# Odbiornik_1.net
KiCad netlist of a schematic drawn in EAGLE
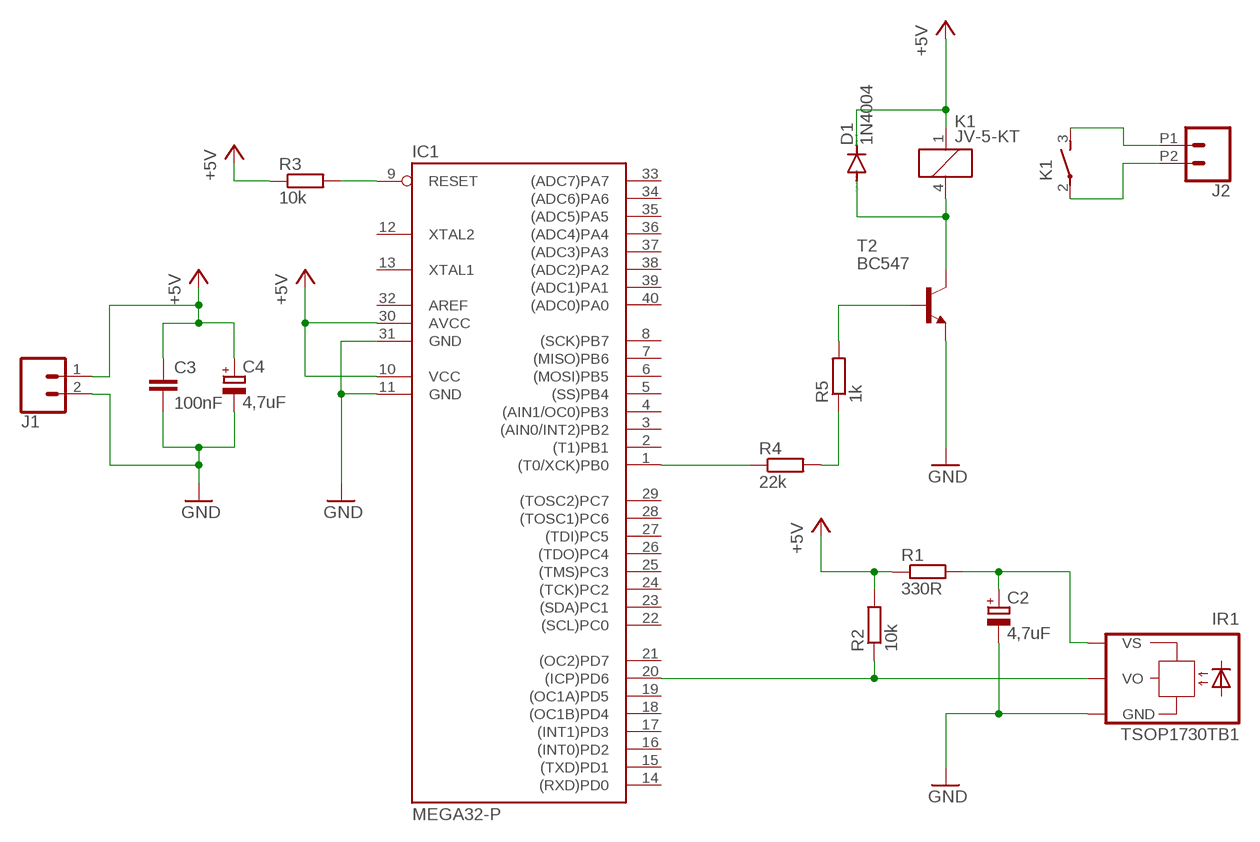
[diagram p0: schematic, sheet 1]

(export (version "E")
  (design (tool "Eeschema 10.0.6"))
  (components
    (comp (ref "C2")
      (value "4,7uF")
      (footprint "eagle-import:E2-4")
      (libsource (lib "eagle-import") (part "CPOL-EUE2-4"))
    )
    (comp (ref "C3")
      (value "100nF")
      (footprint "eagle-import:C025-024X044")
      (libsource (lib "eagle-import") (part "C-EU025-024X044"))
    )
    (comp (ref "C4")
      (value "4,7uF")
      (footprint "eagle-import:E2-4")
      (libsource (lib "eagle-import") (part "CPOL-EUE2-4"))
    )
    (comp (ref "D1")
      (value "1N4004")
      (footprint "eagle-import:DO41-10")
      (libsource (lib "eagle-import") (part "1N4004"))
    )
    (comp (ref "IC1")
      (value "MEGA32-P")
      (footprint "eagle-import:DIL40")
      (fields (field (name "MPN") "ATMEGA32-16PU"))
      (libsource (lib "eagle-import") (part "MEGA32-P"))
    )
    (comp (ref "IR1")
      (value "TSOP1730TB1")
      (footprint "eagle-import:TSOP17_TB1")
      (libsource (lib "eagle-import") (part "TSOP17TB130"))
    )
    (comp (ref "J1")
      (value "CONN_02")
      (footprint "eagle-import:1X02")
      (libsource (lib "eagle-import") (part "CONN_02"))
    )
    (comp (ref "J2")
      (value "CONN_022.54MM_SCREWTERM")
      (footprint "eagle-import:1X02_2.54_SCREWTERM")
      (libsource (lib "eagle-import") (part "CONN_022.54MM_SCREWTERM"))
    )
    (comp (ref "K1")
      (value "JV-5-KT")
      (footprint "eagle-import:JV-KT")
      (libsource (lib "eagle-import") (part "JV-KT-5"))
    )
    (comp (ref "R1")
      (value "330R")
      (footprint "eagle-import:0204_5")
      (libsource (lib "eagle-import") (part "R-EU_0204/5"))
    )
    (comp (ref "R2")
      (value "10k")
      (footprint "eagle-import:0204_5")
      (libsource (lib "eagle-import") (part "R-EU_0204/5"))
    )
    (comp (ref "R3")
      (value "10k")
      (footprint "eagle-import:0204_5")
      (libsource (lib "eagle-import") (part "R-EU_0204/5"))
    )
    (comp (ref "R4")
      (value "22k")
      (footprint "eagle-import:0204_5")
      (libsource (lib "eagle-import") (part "R-EU_0204/5"))
    )
    (comp (ref "R5")
      (value "1k")
      (footprint "eagle-import:0204_5")
      (libsource (lib "eagle-import") (part "R-EU_0204/5"))
    )
    (comp (ref "T2")
      (value "BC547")
      (footprint "eagle-import:TO92")
      (libsource (lib "eagle-import") (part "BC547"))
    )
  )
  (nets
    (net (code "1") (name "+5V") (class "Default")
      (node (ref "C3") (pin "1") (pinfunction "1_1") (pintype "passive"))
      (node (ref "C4") (pin "+") (pinfunction "+_+") (pintype "passive"))
      (node (ref "D1") (pin "C") (pinfunction "C_C") (pintype "passive"))
      (node (ref "IC1") (pin "10") (pinfunction "VCC_10") (pintype "power_in"))
      (node (ref "IC1") (pin "30") (pinfunction "AVCC_30") (pintype "power_in"))
      (node (ref "J1") (pin "1") (pinfunction "1_1") (pintype "passive"))
      (node (ref "K1") (pin "1") (pinfunction "1_1") (pintype "passive"))
      (node (ref "R1") (pin "1") (pinfunction "1_1") (pintype "passive"))
      (node (ref "R2") (pin "2") (pinfunction "2_2") (pintype "passive"))
      (node (ref "R3") (pin "1") (pinfunction "1_1") (pintype "passive"))
    )
    (net (code "2") (name "GND") (class "Default")
      (node (ref "C2") (pin "-") (pinfunction "-_-") (pintype "passive"))
      (node (ref "C3") (pin "2") (pinfunction "2_2") (pintype "passive"))
      (node (ref "C4") (pin "-") (pinfunction "-_-") (pintype "passive"))
      (node (ref "IC1") (pin "11") (pinfunction "GND_11") (pintype "power_in"))
      (node (ref "IC1") (pin "31") (pinfunction "GND_31") (pintype "power_in"))
      (node (ref "IR1") (pin "GND") (pinfunction "GND_GND") (pintype "power_in"))
      (node (ref "J1") (pin "2") (pinfunction "2_2") (pintype "passive"))
      (node (ref "T2") (pin "1") (pinfunction "E_1") (pintype "passive"))
    )
    (net (code "3") (name "Net-(C2-Pad+)") (class "Default")
      (node (ref "C2") (pin "+") (pinfunction "+_+") (pintype "passive"))
      (node (ref "IR1") (pin "VS") (pinfunction "VS_VS") (pintype "power_in"))
      (node (ref "R1") (pin "2") (pinfunction "2_2") (pintype "passive"))
    )
    (net (code "4") (name "Net-(IC1-(ICP)PD6)") (class "Default")
      (node (ref "IC1") (pin "20") (pinfunction "(ICP)PD6_20") (pintype "bidirectional"))
      (node (ref "IR1") (pin "VO") (pinfunction "VO_VO") (pintype "open_collector"))
      (node (ref "R2") (pin "1") (pinfunction "1_1") (pintype "passive"))
    )
    (net (code "5") (name "Net-(IC1-(T0{slash}XCK)PB0)") (class "Default")
      (node (ref "IC1") (pin "1") (pinfunction "(T0/XCK)PB0_1") (pintype "bidirectional"))
      (node (ref "R4") (pin "1") (pinfunction "1_1") (pintype "passive"))
    )
    (net (code "6") (name "Net-(IC1-RESET)") (class "Default")
      (node (ref "IC1") (pin "9") (pinfunction "RESET_9") (pintype "input"))
      (node (ref "R3") (pin "2") (pinfunction "2_2") (pintype "passive"))
    )
    (net (code "7") (name "Net-(J2-1)") (class "Default")
      (node (ref "J2") (pin "P1") (pinfunction "1_P1") (pintype "passive"))
      (node (ref "K1") (pin "3") (pinfunction "S_3") (pintype "passive"))
    )
    (net (code "8") (name "Net-(J2-2)") (class "Default")
      (node (ref "J2") (pin "P2") (pinfunction "2_P2") (pintype "passive"))
      (node (ref "K1") (pin "2") (pinfunction "P_2") (pintype "passive"))
    )
    (net (code "9") (name "Net-(K1A-2)") (class "Default")
      (node (ref "D1") (pin "A") (pinfunction "A_A") (pintype "passive"))
      (node (ref "K1") (pin "4") (pinfunction "2_4") (pintype "passive"))
      (node (ref "T2") (pin "3") (pinfunction "C_3") (pintype "passive"))
    )
    (net (code "10") (name "Net-(R4-Pad2)") (class "Default")
      (node (ref "R4") (pin "2") (pinfunction "2_2") (pintype "passive"))
      (node (ref "R5") (pin "1") (pinfunction "1_1") (pintype "passive"))
    )
    (net (code "11") (name "Net-(T2-B)") (class "Default")
      (node (ref "R5") (pin "2") (pinfunction "2_2") (pintype "passive"))
      (node (ref "T2") (pin "2") (pinfunction "B_2") (pintype "passive"))
    )
    (net (code "12") (name "unconnected-(IC1-(ADC0)PA0-Pad40)") (class "Default")
      (node (ref "IC1") (pin "40") (pinfunction "(ADC0)PA0_40") (pintype "bidirectional"))
    )
    (net (code "13") (name "unconnected-(IC1-(ADC1)PA1-Pad39)") (class "Default")
      (node (ref "IC1") (pin "39") (pinfunction "(ADC1)PA1_39") (pintype "bidirectional"))
    )
    (net (code "14") (name "unconnected-(IC1-(ADC2)PA2-Pad38)") (class "Default")
      (node (ref "IC1") (pin "38") (pinfunction "(ADC2)PA2_38") (pintype "bidirectional"))
    )
    (net (code "15") (name "unconnected-(IC1-(ADC3)PA3-Pad37)") (class "Default")
      (node (ref "IC1") (pin "37") (pinfunction "(ADC3)PA3_37") (pintype "bidirectional"))
    )
    (net (code "16") (name "unconnected-(IC1-(ADC4)PA4-Pad36)") (class "Default")
      (node (ref "IC1") (pin "36") (pinfunction "(ADC4)PA4_36") (pintype "bidirectional"))
    )
    (net (code "17") (name "unconnected-(IC1-(ADC5)PA5-Pad35)") (class "Default")
      (node (ref "IC1") (pin "35") (pinfunction "(ADC5)PA5_35") (pintype "bidirectional"))
    )
    (net (code "18") (name "unconnected-(IC1-(ADC6)PA6-Pad34)") (class "Default")
      (node (ref "IC1") (pin "34") (pinfunction "(ADC6)PA6_34") (pintype "bidirectional"))
    )
    (net (code "19") (name "unconnected-(IC1-(ADC7)PA7-Pad33)") (class "Default")
      (node (ref "IC1") (pin "33") (pinfunction "(ADC7)PA7_33") (pintype "bidirectional"))
    )
    (net (code "20") (name "unconnected-(IC1-(AIN0{slash}INT2)PB2-Pad3)") (class "Default")
      (node (ref "IC1") (pin "3") (pinfunction "(AIN0/INT2)PB2_3") (pintype "bidirectional"))
    )
    (net (code "21") (name "unconnected-(IC1-(AIN1{slash}OC0)PB3-Pad4)") (class "Default")
      (node (ref "IC1") (pin "4") (pinfunction "(AIN1/OC0)PB3_4") (pintype "bidirectional"))
    )
    (net (code "22") (name "unconnected-(IC1-(INT0)PD2-Pad16)") (class "Default")
      (node (ref "IC1") (pin "16") (pinfunction "(INT0)PD2_16") (pintype "bidirectional"))
    )
    (net (code "23") (name "unconnected-(IC1-(INT1)PD3-Pad17)") (class "Default")
      (node (ref "IC1") (pin "17") (pinfunction "(INT1)PD3_17") (pintype "bidirectional"))
    )
    (net (code "24") (name "unconnected-(IC1-(MISO)PB6-Pad7)") (class "Default")
      (node (ref "IC1") (pin "7") (pinfunction "(MISO)PB6_7") (pintype "bidirectional"))
    )
    (net (code "25") (name "unconnected-(IC1-(MOSI)PB5-Pad6)") (class "Default")
      (node (ref "IC1") (pin "6") (pinfunction "(MOSI)PB5_6") (pintype "bidirectional"))
    )
    (net (code "26") (name "unconnected-(IC1-(OC1A)PD5-Pad19)") (class "Default")
      (node (ref "IC1") (pin "19") (pinfunction "(OC1A)PD5_19") (pintype "bidirectional"))
    )
    (net (code "27") (name "unconnected-(IC1-(OC1B)PD4-Pad18)") (class "Default")
      (node (ref "IC1") (pin "18") (pinfunction "(OC1B)PD4_18") (pintype "bidirectional"))
    )
    (net (code "28") (name "unconnected-(IC1-(OC2)PD7-Pad21)") (class "Default")
      (node (ref "IC1") (pin "21") (pinfunction "(OC2)PD7_21") (pintype "bidirectional"))
    )
    (net (code "29") (name "unconnected-(IC1-(RXD)PD0-Pad14)") (class "Default")
      (node (ref "IC1") (pin "14") (pinfunction "(RXD)PD0_14") (pintype "bidirectional"))
    )
    (net (code "30") (name "unconnected-(IC1-(SCK)PB7-Pad8)") (class "Default")
      (node (ref "IC1") (pin "8") (pinfunction "(SCK)PB7_8") (pintype "bidirectional"))
    )
    (net (code "31") (name "unconnected-(IC1-(SCL)PC0-Pad22)") (class "Default")
      (node (ref "IC1") (pin "22") (pinfunction "(SCL)PC0_22") (pintype "bidirectional"))
    )
    (net (code "32") (name "unconnected-(IC1-(SDA)PC1-Pad23)") (class "Default")
      (node (ref "IC1") (pin "23") (pinfunction "(SDA)PC1_23") (pintype "bidirectional"))
    )
    (net (code "33") (name "unconnected-(IC1-(SS)PB4-Pad5)") (class "Default")
      (node (ref "IC1") (pin "5") (pinfunction "(SS)PB4_5") (pintype "bidirectional"))
    )
    (net (code "34") (name "unconnected-(IC1-(T1)PB1-Pad2)") (class "Default")
      (node (ref "IC1") (pin "2") (pinfunction "(T1)PB1_2") (pintype "bidirectional"))
    )
    (net (code "35") (name "unconnected-(IC1-(TCK)PC2-Pad24)") (class "Default")
      (node (ref "IC1") (pin "24") (pinfunction "(TCK)PC2_24") (pintype "bidirectional"))
    )
    (net (code "36") (name "unconnected-(IC1-(TDI)PC5-Pad27)") (class "Default")
      (node (ref "IC1") (pin "27") (pinfunction "(TDI)PC5_27") (pintype "bidirectional"))
    )
    (net (code "37") (name "unconnected-(IC1-(TDO)PC4-Pad26)") (class "Default")
      (node (ref "IC1") (pin "26") (pinfunction "(TDO)PC4_26") (pintype "bidirectional"))
    )
    (net (code "38") (name "unconnected-(IC1-(TMS)PC3-Pad25)") (class "Default")
      (node (ref "IC1") (pin "25") (pinfunction "(TMS)PC3_25") (pintype "bidirectional"))
    )
    (net (code "39") (name "unconnected-(IC1-(TOSC1)PC6-Pad28)") (class "Default")
      (node (ref "IC1") (pin "28") (pinfunction "(TOSC1)PC6_28") (pintype "bidirectional"))
    )
    (net (code "40") (name "unconnected-(IC1-(TOSC2)PC7-Pad29)") (class "Default")
      (node (ref "IC1") (pin "29") (pinfunction "(TOSC2)PC7_29") (pintype "bidirectional"))
    )
    (net (code "41") (name "unconnected-(IC1-(TXD)PD1-Pad15)") (class "Default")
      (node (ref "IC1") (pin "15") (pinfunction "(TXD)PD1_15") (pintype "bidirectional"))
    )
    (net (code "42") (name "unconnected-(IC1-AREF-Pad32)") (class "Default")
      (node (ref "IC1") (pin "32") (pinfunction "AREF_32") (pintype "passive"))
    )
    (net (code "43") (name "unconnected-(IC1-XTAL1-Pad13)") (class "Default")
      (node (ref "IC1") (pin "13") (pinfunction "XTAL1_13") (pintype "bidirectional"))
    )
    (net (code "44") (name "unconnected-(IC1-XTAL2-Pad12)") (class "Default")
      (node (ref "IC1") (pin "12") (pinfunction "XTAL2_12") (pintype "bidirectional"))
    )
  )
)
